# power.net
KiCad netlist of a schematic drawn in Altium Designer
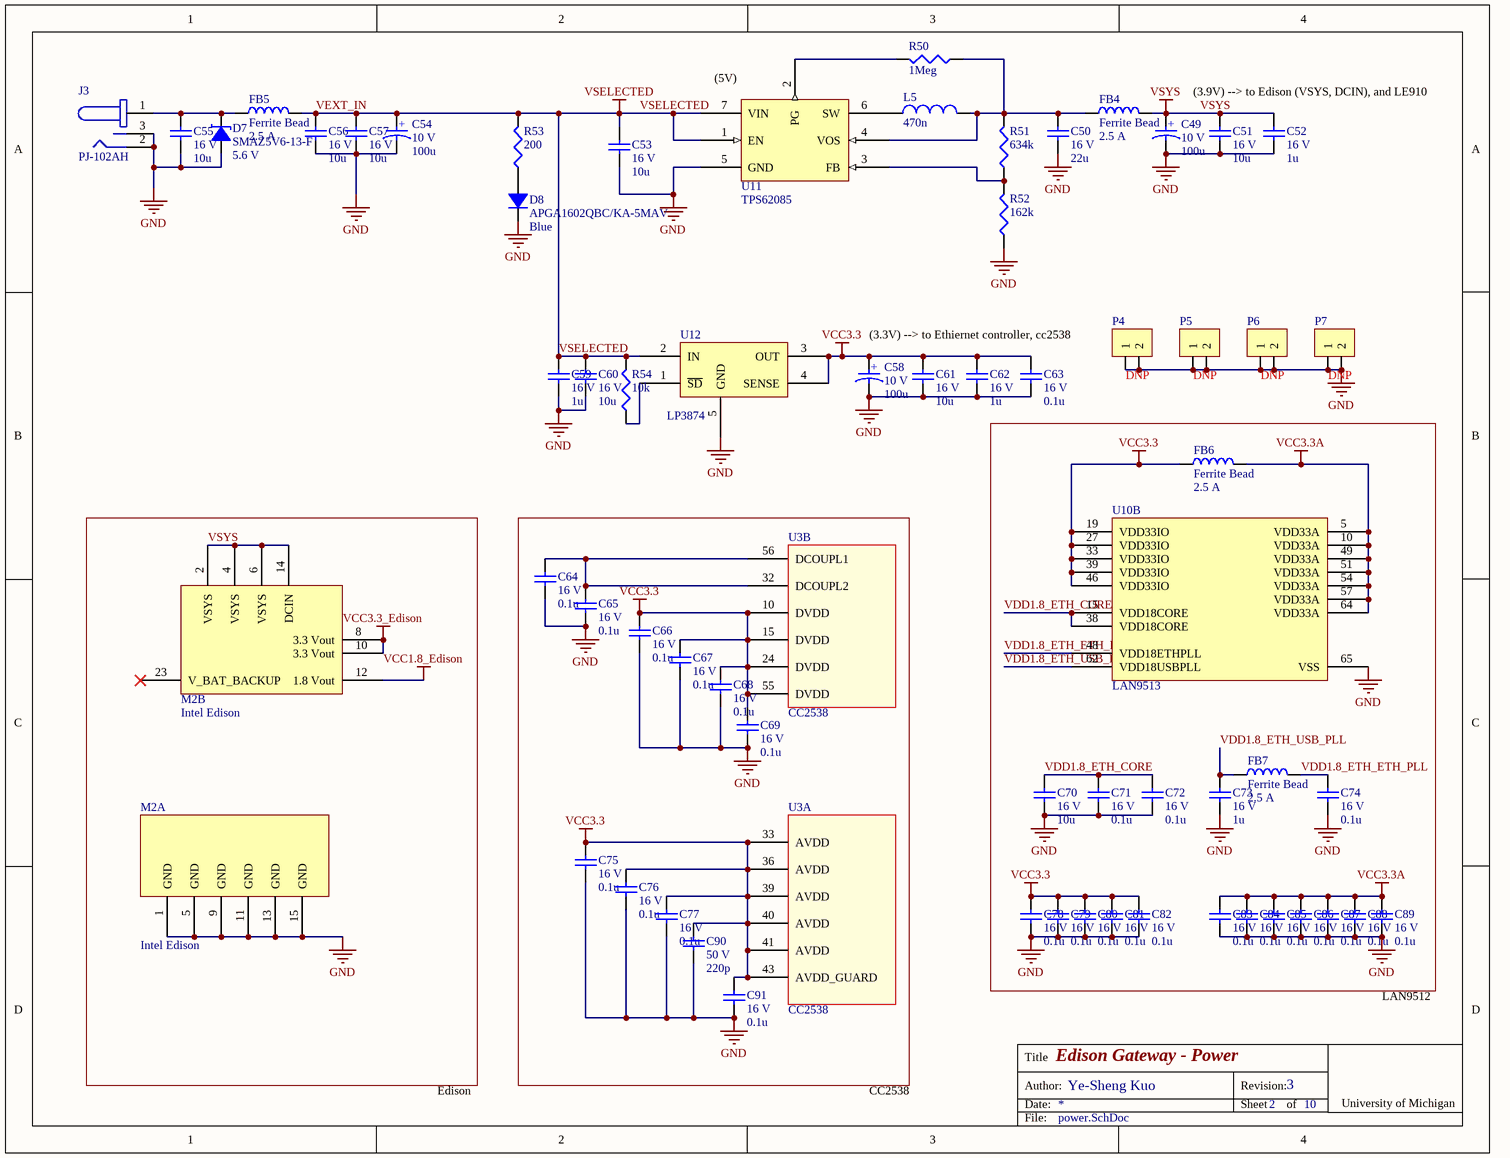
[diagram p0: power.SchDoc]

(export (version "E")
  (design (tool "Eeschema 10.0.6"))
  (components
    (comp (ref "C49")
      (value "100u")
      (footprint "1206 - POLAR MARKING")
      (description "100µF ±20% Molded Tantalum Capacitors 10V 1206")
      (fields
        (field (name "TOLERANCE") "20%")
        (field (name "VOLTAGE RATED") "10 V")
        (field (name "MANUFACTURER PART NUMBER") "TLNK107M010R2500")
      )
      (libsource (lib "capacitors") (part "TLNK107M010R2500"))
    )
    (comp (ref "C50")
      (value "22u")
      (footprint "1206")
      (description "22µF ±20% 16V Ceramic Capacitor X5R 1206")
      (fields
        (field (name "TOLERANCE") "20%")
        (field (name "VOLTAGE RATED") "16 V")
        (field (name "MANUFACTURER PART NUMBER") "CL31A226MOCLNNC")
      )
      (libsource (lib "capacitors") (part "CL31A226MOCLNNC"))
    )
    (comp (ref "C51")
      (value "10u")
      (footprint "0603")
      (description "10µF ±20% 16V Ceramic Capacitor X6S 0603")
      (fields
        (field (name "TOLERANCE") "20%")
        (field (name "VOLTAGE RATED") "16 V")
        (field (name "MANUFACTURER PART NUMBER") "GRM188C81C106MA73D")
      )
      (libsource (lib "capacitors") (part "GRM188C81C106MA73D"))
    )
    (comp (ref "C52")
      (value "1u")
      (footprint "0402")
      (description "1µF ±10% 16V Ceramic Capacitor X6S 0402")
      (fields
        (field (name "TOLERANCE") "10%")
        (field (name "VOLTAGE RATED") "16 V")
        (field (name "MANUFACTURER PART NUMBER") "C1005X6S1C105K050BC")
      )
      (libsource (lib "capacitors") (part "C1005X6S1C105K050BC"))
    )
    (comp (ref "C53")
      (value "10u")
      (footprint "0603")
      (description "10µF ±20% 16V Ceramic Capacitor X6S 0603")
      (fields
        (field (name "TOLERANCE") "20%")
        (field (name "VOLTAGE RATED") "16 V")
        (field (name "MANUFACTURER PART NUMBER") "GRM188C81C106MA73D")
      )
      (libsource (lib "capacitors") (part "GRM188C81C106MA73D"))
    )
    (comp (ref "C54")
      (value "100u")
      (footprint "1206 - POLAR MARKING")
      (description "100µF ±20% Molded Tantalum Capacitors 10V 1206")
      (fields
        (field (name "TOLERANCE") "20%")
        (field (name "MANUFACTURER PART NUMBER") "TLNK107M010R2500")
        (field (name "VOLTAGE RATED") "10 V")
      )
      (libsource (lib "capacitors") (part "TLNK107M010R2500"))
    )
    (comp (ref "C55")
      (value "10u")
      (footprint "0603")
      (description "10µF ±20% 16V Ceramic Capacitor X6S 0603")
      (fields
        (field (name "TOLERANCE") "20%")
        (field (name "VOLTAGE RATED") "16 V")
        (field (name "MANUFACTURER PART NUMBER") "GRM188C81C106MA73D")
      )
      (libsource (lib "capacitors") (part "GRM188C81C106MA73D"))
    )
    (comp (ref "C56")
      (value "10u")
      (footprint "0603")
      (description "10µF ±20% 16V Ceramic Capacitor X6S 0603")
      (fields
        (field (name "TOLERANCE") "20%")
        (field (name "VOLTAGE RATED") "16 V")
        (field (name "MANUFACTURER PART NUMBER") "GRM188C81C106MA73D")
      )
      (libsource (lib "capacitors") (part "GRM188C81C106MA73D"))
    )
    (comp (ref "C57")
      (value "10u")
      (footprint "0603")
      (description "10µF ±20% 16V Ceramic Capacitor X6S 0603")
      (fields
        (field (name "TOLERANCE") "20%")
        (field (name "VOLTAGE RATED") "16 V")
        (field (name "MANUFACTURER PART NUMBER") "GRM188C81C106MA73D")
      )
      (libsource (lib "capacitors") (part "GRM188C81C106MA73D"))
    )
    (comp (ref "C58")
      (value "100u")
      (footprint "1206 - POLAR MARKING")
      (description "100µF ±20% Molded Tantalum Capacitors 10V 1206")
      (fields
        (field (name "TOLERANCE") "20%")
        (field (name "VOLTAGE RATED") "10 V")
        (field (name "MANUFACTURER PART NUMBER") "TLNK107M010R2500")
      )
      (libsource (lib "capacitors") (part "TLNK107M010R2500"))
    )
    (comp (ref "C59")
      (value "1u")
      (footprint "0402")
      (description "1µF ±10% 16V Ceramic Capacitor X6S 0402")
      (fields
        (field (name "TOLERANCE") "10%")
        (field (name "VOLTAGE RATED") "16 V")
        (field (name "MANUFACTURER PART NUMBER") "C1005X6S1C105K050BC")
      )
      (libsource (lib "capacitors") (part "C1005X6S1C105K050BC"))
    )
    (comp (ref "C60")
      (value "10u")
      (footprint "0603")
      (description "10µF ±20% 16V Ceramic Capacitor X6S 0603")
      (fields
        (field (name "TOLERANCE") "20%")
        (field (name "VOLTAGE RATED") "16 V")
        (field (name "MANUFACTURER PART NUMBER") "GRM188C81C106MA73D")
      )
      (libsource (lib "capacitors") (part "GRM188C81C106MA73D"))
    )
    (comp (ref "C61")
      (value "10u")
      (footprint "0603")
      (description "10µF ±20% 16V Ceramic Capacitor X6S 0603")
      (fields
        (field (name "TOLERANCE") "20%")
        (field (name "VOLTAGE RATED") "16 V")
        (field (name "MANUFACTURER PART NUMBER") "GRM188C81C106MA73D")
      )
      (libsource (lib "capacitors") (part "GRM188C81C106MA73D"))
    )
    (comp (ref "C62")
      (value "1u")
      (footprint "0402")
      (description "1µF ±10% 16V Ceramic Capacitor X6S 0402")
      (fields
        (field (name "TOLERANCE") "10%")
        (field (name "VOLTAGE RATED") "16 V")
        (field (name "MANUFACTURER PART NUMBER") "C1005X6S1C105K050BC")
      )
      (libsource (lib "capacitors") (part "C1005X6S1C105K050BC"))
    )
    (comp (ref "C63")
      (value "0.1u")
      (footprint "0402")
      (description "0.10µF ±10% 16V Ceramic Capacitor X7R 0402")
      (fields
        (field (name "TOLERANCE") "10%")
        (field (name "VOLTAGE RATED") "16 V")
        (field (name "MANUFACTURER PART NUMBER") "GRM155R71C104KA88D")
      )
      (libsource (lib "capacitors") (part "GRM155R71C104KA88D"))
    )
    (comp (ref "C64")
      (value "0.1u")
      (footprint "0402")
      (description "0.10µF ±10% 16V Ceramic Capacitor X7R 0402")
      (fields
        (field (name "VOLTAGE RATED") "16 V")
        (field (name "TOLERANCE") "10%")
        (field (name "MANUFACTURER PART NUMBER") "GRM155R71C104KA88D")
      )
      (libsource (lib "capacitors") (part "GRM155R71C104KA88D"))
    )
    (comp (ref "C65")
      (value "0.1u")
      (footprint "0402")
      (description "0.10µF ±10% 16V Ceramic Capacitor X7R 0402")
      (fields
        (field (name "VOLTAGE RATED") "16 V")
        (field (name "TOLERANCE") "10%")
        (field (name "MANUFACTURER PART NUMBER") "GRM155R71C104KA88D")
      )
      (libsource (lib "capacitors") (part "GRM155R71C104KA88D"))
    )
    (comp (ref "C66")
      (value "0.1u")
      (footprint "0402")
      (description "0.10µF ±10% 16V Ceramic Capacitor X7R 0402")
      (fields
        (field (name "VOLTAGE RATED") "16 V")
        (field (name "TOLERANCE") "10%")
        (field (name "MANUFACTURER PART NUMBER") "GRM155R71C104KA88D")
      )
      (libsource (lib "capacitors") (part "GRM155R71C104KA88D"))
    )
    (comp (ref "C67")
      (value "0.1u")
      (footprint "0402")
      (description "0.10µF ±10% 16V Ceramic Capacitor X7R 0402")
      (fields
        (field (name "VOLTAGE RATED") "16 V")
        (field (name "TOLERANCE") "10%")
        (field (name "MANUFACTURER PART NUMBER") "GRM155R71C104KA88D")
      )
      (libsource (lib "capacitors") (part "GRM155R71C104KA88D"))
    )
    (comp (ref "C68")
      (value "0.1u")
      (footprint "0402")
      (description "0.10µF ±10% 16V Ceramic Capacitor X7R 0402")
      (fields
        (field (name "VOLTAGE RATED") "16 V")
        (field (name "TOLERANCE") "10%")
        (field (name "MANUFACTURER PART NUMBER") "GRM155R71C104KA88D")
      )
      (libsource (lib "capacitors") (part "GRM155R71C104KA88D"))
    )
    (comp (ref "C69")
      (value "0.1u")
      (footprint "0402")
      (description "0.10µF ±10% 16V Ceramic Capacitor X7R 0402")
      (fields
        (field (name "VOLTAGE RATED") "16 V")
        (field (name "TOLERANCE") "10%")
        (field (name "MANUFACTURER PART NUMBER") "GRM155R71C104KA88D")
      )
      (libsource (lib "capacitors") (part "GRM155R71C104KA88D"))
    )
    (comp (ref "C70")
      (value "10u")
      (footprint "0603")
      (description "10µF ±20% 16V Ceramic Capacitor X6S 0603")
      (fields
        (field (name "TOLERANCE") "20%")
        (field (name "VOLTAGE RATED") "16 V")
        (field (name "MANUFACTURER PART NUMBER") "GRM188C81C106MA73D")
      )
      (libsource (lib "capacitors") (part "GRM188C81C106MA73D"))
    )
    (comp (ref "C71")
      (value "0.1u")
      (footprint "0402")
      (description "0.10µF ±10% 16V Ceramic Capacitor X7R 0402")
      (fields
        (field (name "VOLTAGE RATED") "16 V")
        (field (name "TOLERANCE") "10%")
        (field (name "MANUFACTURER PART NUMBER") "GRM155R71C104KA88D")
      )
      (libsource (lib "capacitors") (part "GRM155R71C104KA88D"))
    )
    (comp (ref "C72")
      (value "0.1u")
      (footprint "0402")
      (description "0.10µF ±10% 16V Ceramic Capacitor X7R 0402")
      (fields
        (field (name "VOLTAGE RATED") "16 V")
        (field (name "TOLERANCE") "10%")
        (field (name "MANUFACTURER PART NUMBER") "GRM155R71C104KA88D")
      )
      (libsource (lib "capacitors") (part "GRM155R71C104KA88D"))
    )
    (comp (ref "C73")
      (value "1u")
      (footprint "0402")
      (description "1µF ±10% 16V Ceramic Capacitor X6S 0402")
      (fields
        (field (name "VOLTAGE RATED") "16 V")
        (field (name "TOLERANCE") "10%")
        (field (name "MANUFACTURER PART NUMBER") "C1005X6S1C105K050BC")
      )
      (libsource (lib "capacitors") (part "C1005X6S1C105K050BC"))
    )
    (comp (ref "C74")
      (value "0.1u")
      (footprint "0402")
      (description "0.10µF ±10% 16V Ceramic Capacitor X7R 0402")
      (fields
        (field (name "VOLTAGE RATED") "16 V")
        (field (name "TOLERANCE") "10%")
        (field (name "MANUFACTURER PART NUMBER") "GRM155R71C104KA88D")
      )
      (libsource (lib "capacitors") (part "GRM155R71C104KA88D"))
    )
    (comp (ref "C75")
      (value "0.1u")
      (footprint "0402")
      (description "0.10µF ±10% 16V Ceramic Capacitor X7R 0402")
      (fields
        (field (name "VOLTAGE RATED") "16 V")
        (field (name "TOLERANCE") "10%")
        (field (name "MANUFACTURER PART NUMBER") "GRM155R71C104KA88D")
      )
      (libsource (lib "capacitors") (part "GRM155R71C104KA88D"))
    )
    (comp (ref "C76")
      (value "0.1u")
      (footprint "0402")
      (description "0.10µF ±10% 16V Ceramic Capacitor X7R 0402")
      (fields
        (field (name "VOLTAGE RATED") "16 V")
        (field (name "TOLERANCE") "10%")
        (field (name "MANUFACTURER PART NUMBER") "GRM155R71C104KA88D")
      )
      (libsource (lib "capacitors") (part "GRM155R71C104KA88D"))
    )
    (comp (ref "C77")
      (value "0.1u")
      (footprint "0402")
      (description "0.10µF ±10% 16V Ceramic Capacitor X7R 0402")
      (fields
        (field (name "VOLTAGE RATED") "16 V")
        (field (name "TOLERANCE") "10%")
        (field (name "MANUFACTURER PART NUMBER") "GRM155R71C104KA88D")
      )
      (libsource (lib "capacitors") (part "GRM155R71C104KA88D"))
    )
    (comp (ref "C78")
      (value "0.1u")
      (footprint "0402")
      (description "0.10µF ±10% 16V Ceramic Capacitor X7R 0402")
      (fields
        (field (name "VOLTAGE RATED") "16 V")
        (field (name "TOLERANCE") "10%")
        (field (name "MANUFACTURER PART NUMBER") "GRM155R71C104KA88D")
      )
      (libsource (lib "capacitors") (part "GRM155R71C104KA88D"))
    )
    (comp (ref "C79")
      (value "0.1u")
      (footprint "0402")
      (description "0.10µF ±10% 16V Ceramic Capacitor X7R 0402")
      (fields
        (field (name "VOLTAGE RATED") "16 V")
        (field (name "TOLERANCE") "10%")
        (field (name "MANUFACTURER PART NUMBER") "GRM155R71C104KA88D")
      )
      (libsource (lib "capacitors") (part "GRM155R71C104KA88D"))
    )
    (comp (ref "C80")
      (value "0.1u")
      (footprint "0402")
      (description "0.10µF ±10% 16V Ceramic Capacitor X7R 0402")
      (fields
        (field (name "VOLTAGE RATED") "16 V")
        (field (name "TOLERANCE") "10%")
        (field (name "MANUFACTURER PART NUMBER") "GRM155R71C104KA88D")
      )
      (libsource (lib "capacitors") (part "GRM155R71C104KA88D"))
    )
    (comp (ref "C81")
      (value "0.1u")
      (footprint "0402")
      (description "0.10µF ±10% 16V Ceramic Capacitor X7R 0402")
      (fields
        (field (name "VOLTAGE RATED") "16 V")
        (field (name "TOLERANCE") "10%")
        (field (name "MANUFACTURER PART NUMBER") "GRM155R71C104KA88D")
      )
      (libsource (lib "capacitors") (part "GRM155R71C104KA88D"))
    )
    (comp (ref "C82")
      (value "0.1u")
      (footprint "0402")
      (description "0.10µF ±10% 16V Ceramic Capacitor X7R 0402")
      (fields
        (field (name "VOLTAGE RATED") "16 V")
        (field (name "TOLERANCE") "10%")
        (field (name "MANUFACTURER PART NUMBER") "GRM155R71C104KA88D")
      )
      (libsource (lib "capacitors") (part "GRM155R71C104KA88D"))
    )
    (comp (ref "C83")
      (value "0.1u")
      (footprint "0402")
      (description "0.10µF ±10% 16V Ceramic Capacitor X7R 0402")
      (fields
        (field (name "VOLTAGE RATED") "16 V")
        (field (name "TOLERANCE") "10%")
        (field (name "MANUFACTURER PART NUMBER") "GRM155R71C104KA88D")
      )
      (libsource (lib "capacitors") (part "GRM155R71C104KA88D"))
    )
    (comp (ref "C84")
      (value "0.1u")
      (footprint "0402")
      (description "0.10µF ±10% 16V Ceramic Capacitor X7R 0402")
      (fields
        (field (name "VOLTAGE RATED") "16 V")
        (field (name "TOLERANCE") "10%")
        (field (name "MANUFACTURER PART NUMBER") "GRM155R71C104KA88D")
      )
      (libsource (lib "capacitors") (part "GRM155R71C104KA88D"))
    )
    (comp (ref "C85")
      (value "0.1u")
      (footprint "0402")
      (description "0.10µF ±10% 16V Ceramic Capacitor X7R 0402")
      (fields
        (field (name "VOLTAGE RATED") "16 V")
        (field (name "TOLERANCE") "10%")
        (field (name "MANUFACTURER PART NUMBER") "GRM155R71C104KA88D")
      )
      (libsource (lib "capacitors") (part "GRM155R71C104KA88D"))
    )
    (comp (ref "C86")
      (value "0.1u")
      (footprint "0402")
      (description "0.10µF ±10% 16V Ceramic Capacitor X7R 0402")
      (fields
        (field (name "VOLTAGE RATED") "16 V")
        (field (name "TOLERANCE") "10%")
        (field (name "MANUFACTURER PART NUMBER") "GRM155R71C104KA88D")
      )
      (libsource (lib "capacitors") (part "GRM155R71C104KA88D"))
    )
    (comp (ref "C87")
      (value "0.1u")
      (footprint "0402")
      (description "0.10µF ±10% 16V Ceramic Capacitor X7R 0402")
      (fields
        (field (name "VOLTAGE RATED") "16 V")
        (field (name "TOLERANCE") "10%")
        (field (name "MANUFACTURER PART NUMBER") "GRM155R71C104KA88D")
      )
      (libsource (lib "capacitors") (part "GRM155R71C104KA88D"))
    )
    (comp (ref "C88")
      (value "0.1u")
      (footprint "0402")
      (description "0.10µF ±10% 16V Ceramic Capacitor X7R 0402")
      (fields
        (field (name "VOLTAGE RATED") "16 V")
        (field (name "TOLERANCE") "10%")
        (field (name "MANUFACTURER PART NUMBER") "GRM155R71C104KA88D")
      )
      (libsource (lib "capacitors") (part "GRM155R71C104KA88D"))
    )
    (comp (ref "C89")
      (value "0.1u")
      (footprint "0402")
      (description "0.10µF ±10% 16V Ceramic Capacitor X7R 0402")
      (fields
        (field (name "VOLTAGE RATED") "16 V")
        (field (name "TOLERANCE") "10%")
        (field (name "MANUFACTURER PART NUMBER") "GRM155R71C104KA88D")
      )
      (libsource (lib "capacitors") (part "GRM155R71C104KA88D"))
    )
    (comp (ref "C90")
      (value "220p")
      (footprint "0402")
      (description "220pF ±10% 50V Ceramic Capacitor X7R 0402")
      (fields
        (field (name "VOLTAGE RATED") "50 V")
        (field (name "TOLERANCE") "10%")
        (field (name "MANUFACTURER PART NUMBER") "C0402C221K5RACTU")
      )
      (libsource (lib "capacitors") (part "C0402C221K5RACTU"))
    )
    (comp (ref "C91")
      (value "0.1u")
      (footprint "0402")
      (description "0.10µF ±10% 16V Ceramic Capacitor X7R 0402")
      (fields
        (field (name "VOLTAGE RATED") "16 V")
        (field (name "TOLERANCE") "10%")
        (field (name "MANUFACTURER PART NUMBER") "GRM155R71C104KA88D")
      )
      (libsource (lib "capacitors") (part "GRM155R71C104KA88D"))
    )
    (comp (ref "D7")
      (value "SMAZ5V6-13-F")
      (footprint "SMAZ5V1")
      (description "Zener Diode 5.6V 1W ±5% Surface Mount SMA")
      (fields
        (field (name "MANUFACTURER") "Diodes Incorporated")
        (field (name "POWER") "1 W")
        (field (name "ZENER VOLTAGE") "5.6 V")
      )
      (libsource (lib "diodes") (part "SMAZ5V6-13-F"))
    )
    (comp (ref "D8")
      (value "APGA1602QBC/KA-5MAV")
      (footprint "APGA1602")
      (description "Blue 463nm LED Indication - Discrete 2.8V 2-SMD")
      (fields (field (name "MANUFACTURER") "Kingbright") (field (name "ALTIUM_VALUE") "Blue"))
      (libsource (lib "LED") (part "APGA1602QBC/KA-5MAV"))
    )
    (comp (ref "FB4")
      (value "Ferrite Bead")
      (footprint "0603")
      (description "FERRITE BEAD 220 OHM 0603")
      (fields
        (field (name "MANUFACTURER PART NUMBER") "BLM18SG221TN1D")
        (field (name "MANUFACTURER") "Murata")
        (field (name "CURRENT RATING (MAX)") "2.5 A")
      )
      (libsource (lib "ferrite_beads") (part "BLM18SG221TN1D"))
    )
    (comp (ref "FB5")
      (value "Ferrite Bead")
      (footprint "0603")
      (description "FERRITE BEAD 220 OHM 0603")
      (fields
        (field (name "MANUFACTURER PART NUMBER") "BLM18SG221TN1D")
        (field (name "MANUFACTURER") "Murata")
        (field (name "CURRENT RATING (MAX)") "2.5 A")
      )
      (libsource (lib "ferrite_beads") (part "BLM18SG221TN1D"))
    )
    (comp (ref "FB6")
      (value "Ferrite Bead")
      (footprint "0603")
      (description "FERRITE BEAD 220 OHM 0603")
      (fields
        (field (name "MANUFACTURER PART NUMBER") "BLM18SG221TN1D")
        (field (name "MANUFACTURER") "Murata")
        (field (name "CURRENT RATING (MAX)") "2.5 A")
      )
      (libsource (lib "ferrite_beads") (part "BLM18SG221TN1D"))
    )
    (comp (ref "FB7")
      (value "Ferrite Bead")
      (footprint "0603")
      (description "FERRITE BEAD 220 OHM 0603")
      (fields
        (field (name "MANUFACTURER PART NUMBER") "BLM18SG221TN1D")
        (field (name "MANUFACTURER") "Murata")
        (field (name "CURRENT RATING (MAX)") "2.5 A")
      )
      (libsource (lib "ferrite_beads") (part "BLM18SG221TN1D"))
    )
    (comp (ref "J3")
      (value "PJ-102AH")
      (footprint "PJ-102AH")
      (description "CONN PWR JACK 2.1X5.5MM HIGH CUR")
      (libsource (lib "connectors") (part "PJ-102AH"))
    )
    (comp (ref "L5")
      (value "470n")
      (footprint "74404300047")
      (description "470nH Shielded Wirewound Inductor 3.8A 16 mOhm Max 1919 (4848 Metric)")
      (fields (field (name "TOLERANCE") "30%") (field (name "MANUFACTURER PART NUMBER") "74404300047"))
      (libsource (lib "inductors") (part "74404300047"))
    )
    (comp (ref "M2")
      (value "Intel Edison")
      (footprint "Intel Edison mating")
      (libsource (lib "Intel Edison") (part "Intel Edison"))
    )
    (comp (ref "P4")
      (value "1 x 2 header")
      (footprint "1x2 header")
      (description "100 mils standard header")
      (fields (field (name "NOTE") "DNP"))
      (libsource (lib "connectors") (part "1 x 2 header"))
    )
    (comp (ref "P5")
      (value "1 x 2 header")
      (footprint "1x2 header")
      (description "100 mils standard header")
      (fields (field (name "NOTE") "DNP"))
      (libsource (lib "connectors") (part "1 x 2 header"))
    )
    (comp (ref "P6")
      (value "1 x 2 header")
      (footprint "1x2 header")
      (description "100 mils standard header")
      (fields (field (name "NOTE") "DNP"))
      (libsource (lib "connectors") (part "1 x 2 header"))
    )
    (comp (ref "P7")
      (value "1 x 2 header")
      (footprint "1x2 header")
      (description "100 mils standard header")
      (fields (field (name "NOTE") "DNP"))
      (libsource (lib "connectors") (part "1 x 2 header"))
    )
    (comp (ref "R50")
      (value "1Meg")
      (footprint "0402")
      (description "RES SMD 1M OHM 1% 1/16W 0402")
      (fields (field (name "TOLERANCE") "1%") (field (name "POWER") "1/16 W"))
      (libsource (lib "resistors") (part "CRCW04021M00FKED"))
    )
    (comp (ref "R51")
      (value "634k")
      (footprint "0402")
      (description "RES SMD 634K OHM 1% 1/16W 0402")
      (fields (field (name "TOLERANCE") "1%") (field (name "POWER") "1/16 W"))
      (libsource (lib "resistors") (part "CRCW0402634KFKED"))
    )
    (comp (ref "R52")
      (value "162k")
      (footprint "0402")
      (description "RES SMD 162K OHM 1% 1/16W 0402")
      (fields (field (name "TOLERANCE") "1%") (field (name "POWER") "1/16 W"))
      (libsource (lib "resistors") (part "CRCW0402162KFKED"))
    )
    (comp (ref "R53")
      (value "200")
      (footprint "0402")
      (description "RES SMD 200 OHM 1% 1/16W 0402")
      (fields (field (name "TOLERANCE") "1%") (field (name "POWER") "1/16 W"))
      (libsource (lib "resistors") (part "CRCW0402200RFKED"))
    )
    (comp (ref "R54")
      (value "10k")
      (footprint "0402")
      (description "RES SMD 10K OHM 1% 1/16W 0402")
      (fields (field (name "TOLERANCE") "1%") (field (name "POWER") "1/16 W"))
      (libsource (lib "resistors") (part "CRCW040210K0FKED"))
    )
    (comp (ref "U3")
      (value "CC2538")
      (footprint "QFN56")
      (description "A Powerful System-On-Chip for 2.4-GHz IEEE 802.15.4, 6LoWPAN  and ZigBee Applications")
      (libsource (lib "MCU") (part "CC2538"))
    )
    (comp (ref "U10")
      (value "LAN9513")
      (footprint "QFN-64")
      (description "USB 2.0 Hub and 10/100  Ethernet Controller")
      (libsource (lib "ethernet controller") (part "LAN9513"))
    )
    (comp (ref "U11")
      (value "TPS62085")
      (footprint "VSON")
      (description "3-A Step-Down Converter With Hiccup Short-Circuit Protection  In 2 × 2 QFN Package")
      (libsource (lib "voltage regulator") (part "TPS62085"))
    )
    (comp (ref "U12")
      (value "LP3874")
      (footprint "SOT150P700X180-5N")
      (description "LP387x 0.8-A Fast Ultra-Low-Dropout Linear Regulators")
      (libsource (lib "voltage regulator") (part "LP3874"))
    )
  )
  (nets
    (net (code "1") (name "/VDD1.8_ETH_CORE") (class "Default")
      (node (ref "C70") (pin "1") (pintype "passive"))
      (node (ref "C71") (pin "1") (pintype "passive"))
      (node (ref "C72") (pin "1") (pintype "passive"))
      (node (ref "U10") (pin "15") (pinfunction "VDD18CORE_15") (pintype "passive"))
      (node (ref "U10") (pin "38") (pinfunction "VDD18CORE_38") (pintype "passive"))
    )
    (net (code "2") (name "/VDD1.8_ETH_ETH_PLL") (class "Default")
      (node (ref "C74") (pin "1") (pintype "passive"))
      (node (ref "FB7") (pin "1") (pintype "passive"))
      (node (ref "U10") (pin "48") (pinfunction "VDD18ETHPLL_48") (pintype "passive"))
    )
    (net (code "3") (name "/VDD1.8_ETH_USB_PLL") (class "Default")
      (node (ref "C73") (pin "1") (pintype "passive"))
      (node (ref "FB7") (pin "2") (pintype "passive"))
      (node (ref "U10") (pin "62") (pinfunction "VDD18USBPLL_62") (pintype "passive"))
    )
    (net (code "4") (name "GND") (class "Default")
      (node (ref "C49") (pin "2") (pintype "passive"))
      (node (ref "C50") (pin "2") (pintype "passive"))
      (node (ref "C51") (pin "2") (pintype "passive"))
      (node (ref "C52") (pin "2") (pintype "passive"))
      (node (ref "C53") (pin "2") (pintype "passive"))
      (node (ref "C54") (pin "2") (pintype "passive"))
      (node (ref "C55") (pin "2") (pintype "passive"))
      (node (ref "C56") (pin "2") (pintype "passive"))
      (node (ref "C57") (pin "2") (pintype "passive"))
      (node (ref "C58") (pin "2") (pintype "passive"))
      (node (ref "C59") (pin "2") (pintype "passive"))
      (node (ref "C60") (pin "2") (pintype "passive"))
      (node (ref "C61") (pin "2") (pintype "passive"))
      (node (ref "C62") (pin "2") (pintype "passive"))
      (node (ref "C63") (pin "2") (pintype "passive"))
      (node (ref "C64") (pin "2") (pintype "passive"))
      (node (ref "C65") (pin "2") (pintype "passive"))
      (node (ref "C66") (pin "2") (pintype "passive"))
      (node (ref "C67") (pin "2") (pintype "passive"))
      (node (ref "C68") (pin "2") (pintype "passive"))
      (node (ref "C69") (pin "2") (pintype "passive"))
      (node (ref "C70") (pin "2") (pintype "passive"))
      (node (ref "C71") (pin "2") (pintype "passive"))
      (node (ref "C72") (pin "2") (pintype "passive"))
      (node (ref "C73") (pin "2") (pintype "passive"))
      (node (ref "C74") (pin "2") (pintype "passive"))
      (node (ref "C75") (pin "2") (pintype "passive"))
      (node (ref "C76") (pin "2") (pintype "passive"))
      (node (ref "C77") (pin "2") (pintype "passive"))
      (node (ref "C78") (pin "2") (pintype "passive"))
      (node (ref "C79") (pin "2") (pintype "passive"))
      (node (ref "C80") (pin "2") (pintype "passive"))
      (node (ref "C81") (pin "2") (pintype "passive"))
      (node (ref "C82") (pin "2") (pintype "passive"))
      (node (ref "C83") (pin "2") (pintype "passive"))
      (node (ref "C84") (pin "2") (pintype "passive"))
      (node (ref "C85") (pin "2") (pintype "passive"))
      (node (ref "C86") (pin "2") (pintype "passive"))
      (node (ref "C87") (pin "2") (pintype "passive"))
      (node (ref "C88") (pin "2") (pintype "passive"))
      (node (ref "C89") (pin "2") (pintype "passive"))
      (node (ref "C90") (pin "2") (pintype "passive"))
      (node (ref "C91") (pin "2") (pintype "passive"))
      (node (ref "D7") (pin "1") (pintype "passive"))
      (node (ref "D8") (pin "2") (pintype "passive"))
      (node (ref "J3") (pin "2") (pintype "passive"))
      (node (ref "J3") (pin "3") (pintype "passive"))
      (node (ref "M2") (pin "1") (pinfunction "GND_1") (pintype "passive"))
      (node (ref "M2") (pin "11") (pinfunction "GND_11") (pintype "passive"))
      (node (ref "M2") (pin "13") (pinfunction "GND_13") (pintype "passive"))
      (node (ref "M2") (pin "15") (pinfunction "GND_15") (pintype "passive"))
      (node (ref "M2") (pin "5") (pinfunction "GND_5") (pintype "passive"))
      (node (ref "M2") (pin "9") (pinfunction "GND_9") (pintype "passive"))
      (node (ref "P4") (pin "1") (pinfunction "1_1") (pintype "passive"))
      (node (ref "P4") (pin "2") (pinfunction "2_2") (pintype "passive"))
      (node (ref "P5") (pin "1") (pinfunction "1_1") (pintype "passive"))
      (node (ref "P5") (pin "2") (pinfunction "2_2") (pintype "passive"))
      (node (ref "P6") (pin "1") (pinfunction "1_1") (pintype "passive"))
      (node (ref "P6") (pin "2") (pinfunction "2_2") (pintype "passive"))
      (node (ref "P7") (pin "1") (pinfunction "1_1") (pintype "passive"))
      (node (ref "P7") (pin "2") (pinfunction "2_2") (pintype "passive"))
      (node (ref "R52") (pin "2") (pintype "passive"))
      (node (ref "U10") (pin "65") (pinfunction "VSS_65") (pintype "passive"))
      (node (ref "U11") (pin "5") (pinfunction "GND_5") (pintype "power_in"))
      (node (ref "U12") (pin "5") (pinfunction "GND_5") (pintype "passive"))
    )
    (net (code "5") (name "Net-(C55-Pad1)") (class "Default")
      (node (ref "C55") (pin "1") (pintype "passive"))
      (node (ref "D7") (pin "2") (pintype "passive"))
      (node (ref "FB5") (pin "2") (pintype "passive"))
      (node (ref "J3") (pin "1") (pintype "passive"))
    )
    (net (code "6") (name "Net-(D8-Pad1)") (class "Default")
      (node (ref "D8") (pin "1") (pintype "passive"))
      (node (ref "R53") (pin "2") (pintype "passive"))
    )
    (net (code "7") (name "Net-(U3B-DCOUPL1)") (class "Default")
      (node (ref "C64") (pin "1") (pintype "passive"))
      (node (ref "C65") (pin "1") (pintype "passive"))
      (node (ref "U3") (pin "32") (pinfunction "DCOUPL2_32") (pintype "power_in"))
      (node (ref "U3") (pin "56") (pinfunction "DCOUPL1_56") (pintype "power_in"))
    )
    (net (code "8") (name "Net-(U11-FB)") (class "Default")
      (node (ref "R51") (pin "2") (pintype "passive"))
      (node (ref "R52") (pin "1") (pintype "passive"))
      (node (ref "U11") (pin "3") (pinfunction "FB_3") (pintype "input"))
    )
    (net (code "9") (name "Net-(U11-PG)") (class "Default")
      (node (ref "R50") (pin "1") (pintype "passive"))
      (node (ref "U11") (pin "2") (pinfunction "PG_2") (pintype "output"))
    )
    (net (code "10") (name "Net-(U11-SW)") (class "Default")
      (node (ref "L5") (pin "2") (pintype "passive"))
      (node (ref "U11") (pin "6") (pinfunction "SW_6") (pintype "power_in"))
    )
    (net (code "11") (name "Net-(U11-VOS)") (class "Default")
      (node (ref "C50") (pin "1") (pintype "passive"))
      (node (ref "FB4") (pin "2") (pintype "passive"))
      (node (ref "L5") (pin "1") (pintype "passive"))
      (node (ref "R50") (pin "2") (pintype "passive"))
      (node (ref "R51") (pin "1") (pintype "passive"))
      (node (ref "U11") (pin "4") (pinfunction "VOS_4") (pintype "input"))
    )
    (net (code "12") (name "Net-(U12-~{SD})") (class "Default")
      (node (ref "R54") (pin "2") (pintype "passive"))
      (node (ref "U12") (pin "1") (pinfunction "~{SD}_1") (pintype "passive"))
    )
    (net (code "13") (name "VCC1.8_Edison") (class "Default")
      (node (ref "M2") (pin "12") (pinfunction "1.8_Vout_12") (pintype "power_in"))
    )
    (net (code "14") (name "VCC3.3") (class "Default")
      (node (ref "C58") (pin "1") (pintype "passive"))
      (node (ref "C61") (pin "1") (pintype "passive"))
      (node (ref "C62") (pin "1") (pintype "passive"))
      (node (ref "C63") (pin "1") (pintype "passive"))
      (node (ref "C66") (pin "1") (pintype "passive"))
      (node (ref "C67") (pin "1") (pintype "passive"))
      (node (ref "C68") (pin "1") (pintype "passive"))
      (node (ref "C69") (pin "1") (pintype "passive"))
      (node (ref "C75") (pin "1") (pintype "passive"))
      (node (ref "C76") (pin "1") (pintype "passive"))
      (node (ref "C77") (pin "1") (pintype "passive"))
      (node (ref "C78") (pin "1") (pintype "passive"))
      (node (ref "C79") (pin "1") (pintype "passive"))
      (node (ref "C80") (pin "1") (pintype "passive"))
      (node (ref "C81") (pin "1") (pintype "passive"))
      (node (ref "C82") (pin "1") (pintype "passive"))
      (node (ref "C90") (pin "1") (pintype "passive"))
      (node (ref "C91") (pin "1") (pintype "passive"))
      (node (ref "FB6") (pin "2") (pintype "passive"))
      (node (ref "U10") (pin "19") (pinfunction "VDD33IO_19") (pintype "passive"))
      (node (ref "U10") (pin "27") (pinfunction "VDD33IO_27") (pintype "passive"))
      (node (ref "U10") (pin "33") (pinfunction "VDD33IO_33") (pintype "passive"))
      (node (ref "U10") (pin "39") (pinfunction "VDD33IO_39") (pintype "passive"))
      (node (ref "U10") (pin "46") (pinfunction "VDD33IO_46") (pintype "passive"))
      (node (ref "U12") (pin "3") (pinfunction "OUT_3") (pintype "passive"))
      (node (ref "U12") (pin "4") (pinfunction "SENSE_4") (pintype "passive"))
      (node (ref "U3") (pin "10") (pinfunction "DVDD_10") (pintype "power_in"))
      (node (ref "U3") (pin "15") (pinfunction "DVDD_15") (pintype "power_in"))
      (node (ref "U3") (pin "24") (pinfunction "DVDD_24") (pintype "power_in"))
      (node (ref "U3") (pin "33") (pinfunction "AVDD_33") (pintype "power_in"))
      (node (ref "U3") (pin "36") (pinfunction "AVDD_36") (pintype "power_in"))
      (node (ref "U3") (pin "39") (pinfunction "AVDD_39") (pintype "power_in"))
      (node (ref "U3") (pin "40") (pinfunction "AVDD_40") (pintype "power_in"))
      (node (ref "U3") (pin "41") (pinfunction "AVDD_41") (pintype "power_in"))
      (node (ref "U3") (pin "43") (pinfunction "AVDD_GUARD_43") (pintype "power_in"))
      (node (ref "U3") (pin "55") (pinfunction "DVDD_55") (pintype "power_in"))
    )
    (net (code "15") (name "VCC3.3A") (class "Default")
      (node (ref "C83") (pin "1") (pintype "passive"))
      (node (ref "C84") (pin "1") (pintype "passive"))
      (node (ref "C85") (pin "1") (pintype "passive"))
      (node (ref "C86") (pin "1") (pintype "passive"))
      (node (ref "C87") (pin "1") (pintype "passive"))
      (node (ref "C88") (pin "1") (pintype "passive"))
      (node (ref "C89") (pin "1") (pintype "passive"))
      (node (ref "FB6") (pin "1") (pintype "passive"))
      (node (ref "U10") (pin "10") (pinfunction "VDD33A_10") (pintype "passive"))
      (node (ref "U10") (pin "49") (pinfunction "VDD33A_49") (pintype "passive"))
      (node (ref "U10") (pin "5") (pinfunction "VDD33A_5") (pintype "passive"))
      (node (ref "U10") (pin "51") (pinfunction "VDD33A_51") (pintype "passive"))
      (node (ref "U10") (pin "54") (pinfunction "VDD33A_54") (pintype "passive"))
      (node (ref "U10") (pin "57") (pinfunction "VDD33A_57") (pintype "passive"))
      (node (ref "U10") (pin "64") (pinfunction "VDD33A_64") (pintype "passive"))
    )
    (net (code "16") (name "VCC3.3_Edison") (class "Default")
      (node (ref "M2") (pin "10") (pinfunction "3.3_Vout_10") (pintype "power_in"))
      (node (ref "M2") (pin "8") (pinfunction "3.3_Vout_8") (pintype "power_in"))
    )
    (net (code "17") (name "VSELECTED") (class "Default")
      (node (ref "C53") (pin "1") (pintype "passive"))
      (node (ref "C54") (pin "1") (pintype "passive"))
      (node (ref "C56") (pin "1") (pintype "passive"))
      (node (ref "C57") (pin "1") (pintype "passive"))
      (node (ref "C59") (pin "1") (pintype "passive"))
      (node (ref "C60") (pin "1") (pintype "passive"))
      (node (ref "FB5") (pin "1") (pintype "passive"))
      (node (ref "R53") (pin "1") (pintype "passive"))
      (node (ref "R54") (pin "1") (pintype "passive"))
      (node (ref "U11") (pin "1") (pinfunction "EN_1") (pintype "input"))
      (node (ref "U11") (pin "7") (pinfunction "VIN_7") (pintype "power_in"))
      (node (ref "U12") (pin "2") (pinfunction "IN_2") (pintype "passive"))
    )
    (net (code "18") (name "VSYS") (class "Default")
      (node (ref "C49") (pin "1") (pintype "passive"))
      (node (ref "C51") (pin "1") (pintype "passive"))
      (node (ref "C52") (pin "1") (pintype "passive"))
      (node (ref "FB4") (pin "1") (pintype "passive"))
      (node (ref "M2") (pin "14") (pinfunction "DCIN_14") (pintype "passive"))
      (node (ref "M2") (pin "2") (pinfunction "VSYS_2") (pintype "passive"))
      (node (ref "M2") (pin "4") (pinfunction "VSYS_4") (pintype "passive"))
      (node (ref "M2") (pin "6") (pinfunction "VSYS_6") (pintype "passive"))
    )
    (net (code "19") (name "unconnected-(M2B-V_BAT_BACKUP-Pad23)") (class "Default")
      (node (ref "M2") (pin "23") (pinfunction "V_BAT_BACKUP_23") (pintype "power_in+no_connect"))
    )
  )
)
